# A300_Backplane.net
KiCad netlist of a schematic drawn in Altium Designer
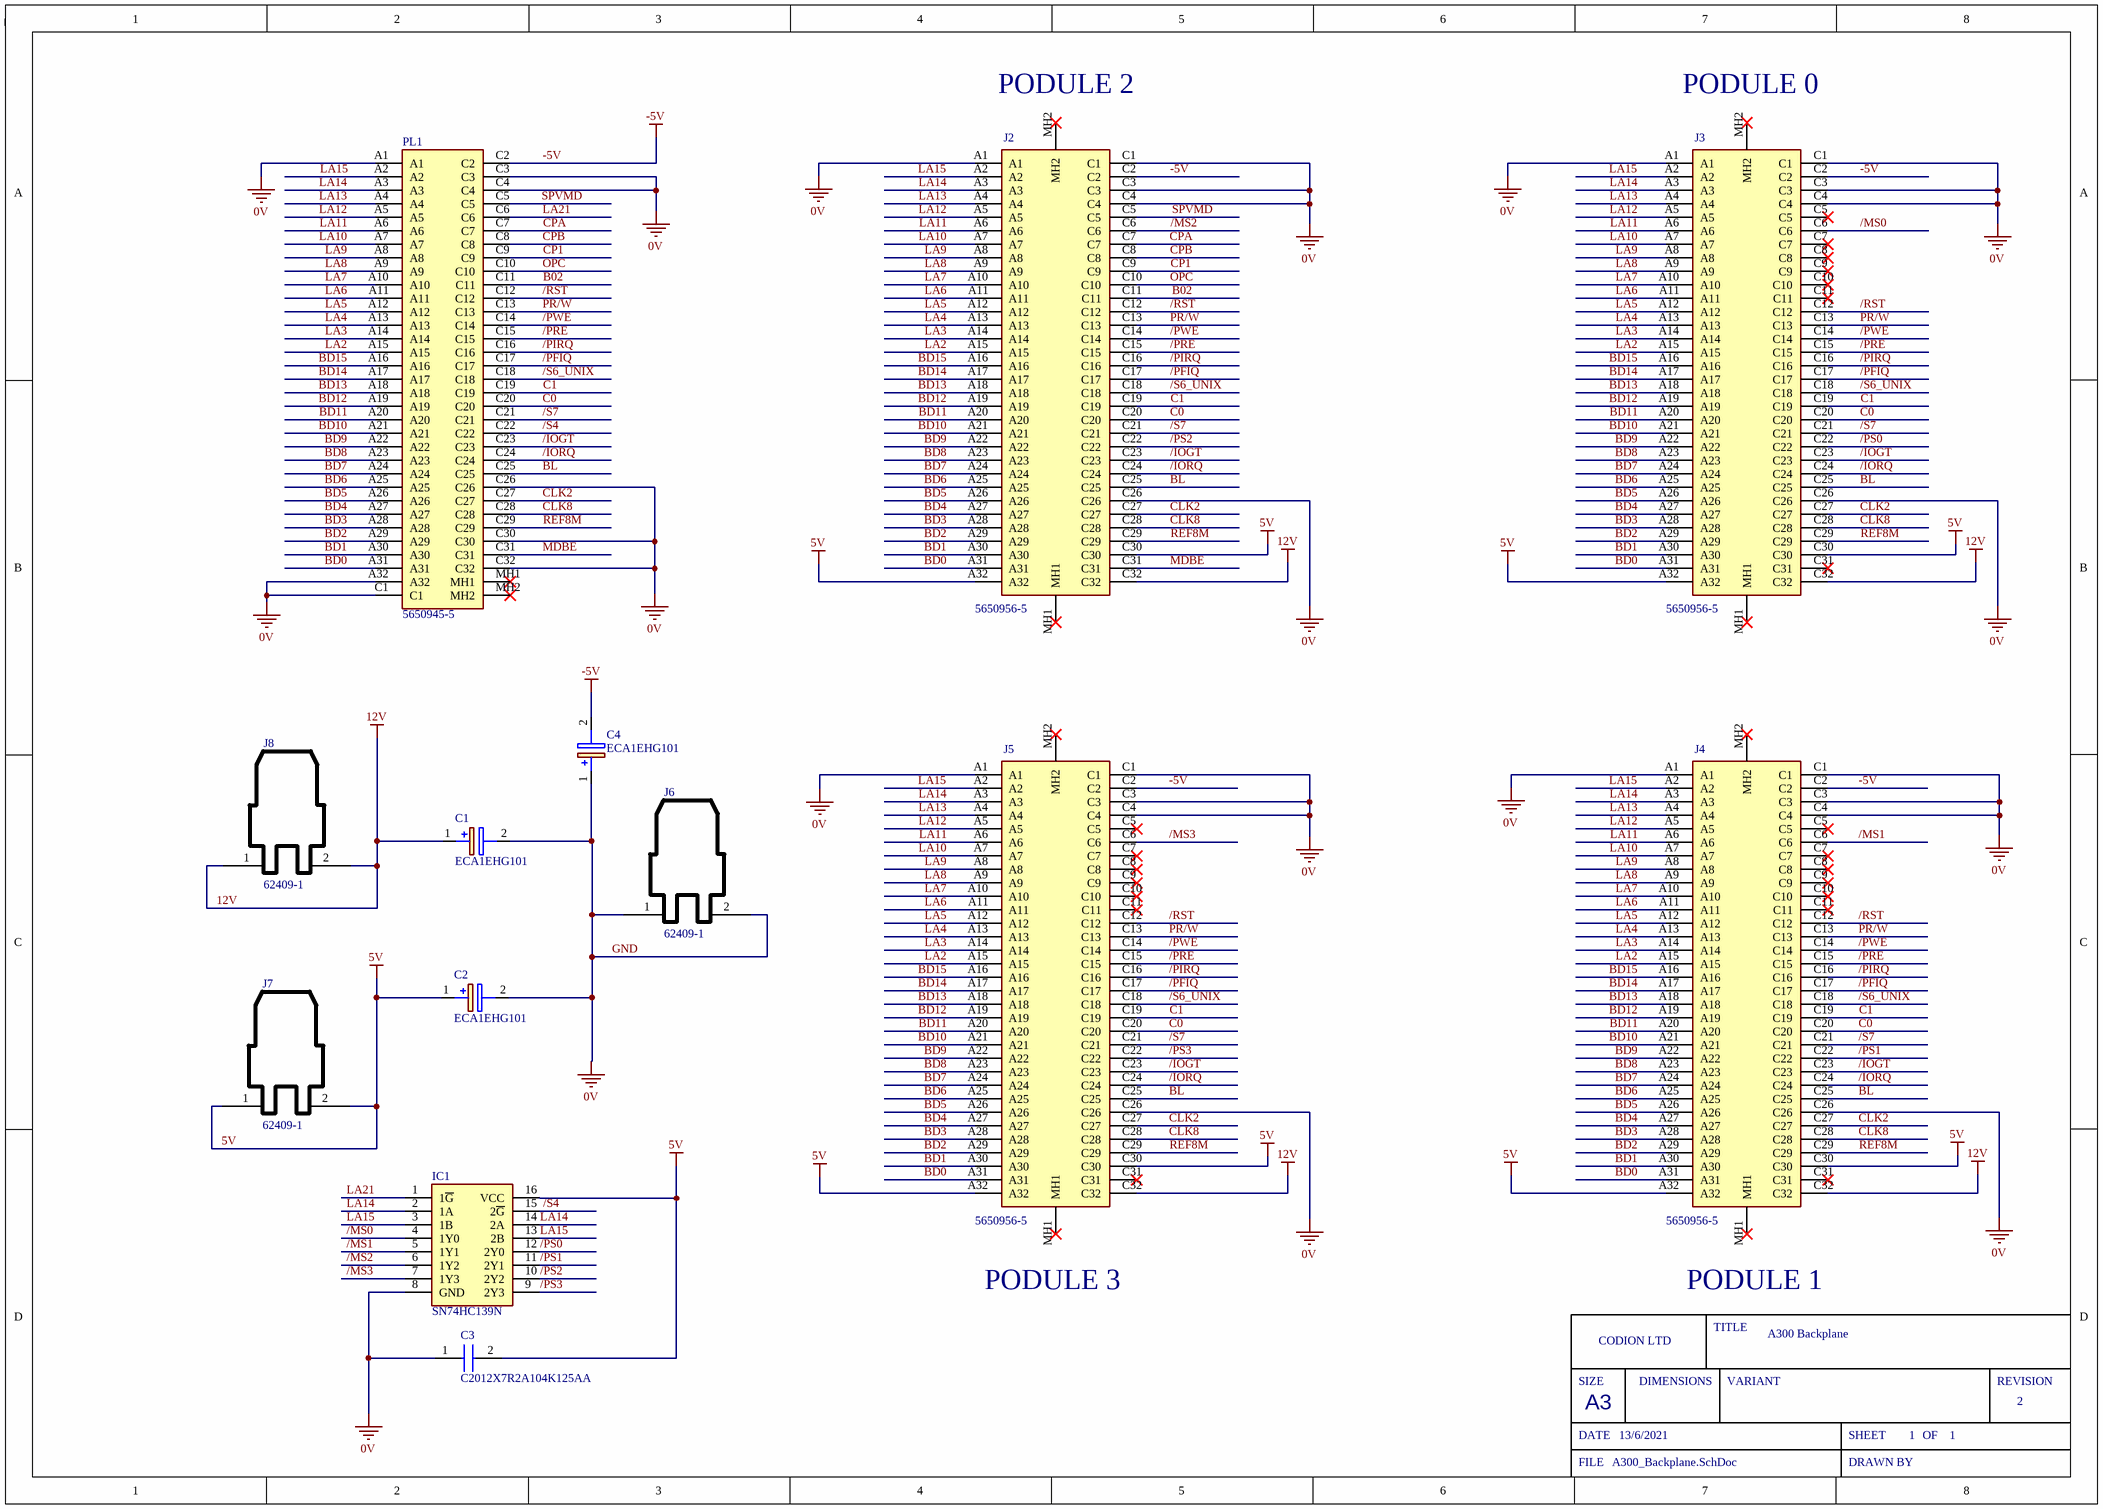
[diagram p0: A300_Backplane.SchDoc]

(export (version "E")
  (design (tool "Eeschema 10.0.6"))
  (components
    (comp (ref "C1")
      (value "ECA1EHG101")
      (footprint "SamacSys:CAPPRD250W55D630H1220")
      (description "Capacitor Polarised")
      (libsource (lib "") (part "ECA1EHG101_1"))
    )
    (comp (ref "C2")
      (value "ECA1EHG101")
      (footprint "SamacSys:CAPPRD250W55D630H1220")
      (description "Capacitor Polarised")
      (libsource (lib "") (part "ECA1EHG101_1"))
    )
    (comp (ref "C3")
      (value "C2012X7R2A104K125AA")
      (footprint "SamacSys:CAPC2012X145N")
      (description "Capacitor")
      (fields (field (name "MOUSER PART NUMBER") "810-C2012X7R2A104K"))
      (libsource (lib "*") (part "C2012X7R2A104K125AA"))
    )
    (comp (ref "C4")
      (value "ECA1EHG101")
      (footprint "SamacSys:CAPPRD250W55D630H1220")
      (description "Capacitor Polarised")
      (libsource (lib "*") (part "ECA1EHG101"))
    )
    (comp (ref "IC1")
      (value "SN74HC139N")
      (footprint "SamacSys:DIP794W53P254L1930H508Q16N")
      (description "Integrated Circuit")
      (fields (field (name "MOUSER PART NUMBER") "595-SN74HC139N"))
      (libsource (lib "*") (part "SN74HC139N"))
    )
    (comp (ref "J2")
      (value "5650956-5")
      (footprint "SamacSys:56509565")
      (description "Connector")
      (fields (field (name "MOUSER PART NUMBER") "571-5650956-5"))
      (libsource (lib "*") (part "5650956-5"))
    )
    (comp (ref "J3")
      (value "5650956-5")
      (footprint "SamacSys:56509565")
      (description "Connector")
      (fields (field (name "MOUSER PART NUMBER") "571-5650956-5"))
      (libsource (lib "*") (part "5650956-5"))
    )
    (comp (ref "J4")
      (value "5650956-5")
      (footprint "SamacSys:56509565")
      (description "Connector")
      (fields (field (name "MOUSER PART NUMBER") "571-5650956-5"))
      (libsource (lib "*") (part "5650956-5"))
    )
    (comp (ref "J5")
      (value "5650956-5")
      (footprint "SamacSys:56509565")
      (description "Connector")
      (fields (field (name "MOUSER PART NUMBER") "571-5650956-5"))
      (libsource (lib "*") (part "5650956-5"))
    )
    (comp (ref "J6")
      (value "62409-1")
      (footprint "62409-1")
      (description "PCB Terminal, 6.35mm x 0.81mm, 0.25\" x 0.032\", Brass, 1.4 mm, Tin")
      (fields (field (name "PART NUMBER") "982-0022") (field (name "MANUFACTURER") "TE Coonectivity"))
      (libsource (lib "Local_Altium_Lib") (part "62409-1"))
    )
    (comp (ref "J7")
      (value "62409-1")
      (footprint "62409-1")
      (description "PCB Terminal, 6.35mm x 0.81mm, 0.25\" x 0.032\", Brass, 1.4 mm, Tin")
      (fields (field (name "PART NUMBER") "982-0022") (field (name "MANUFACTURER") "TE Coonectivity"))
      (libsource (lib "Local_Altium_Lib") (part "62409-1"))
    )
    (comp (ref "J8")
      (value "62409-1")
      (footprint "62409-1")
      (description "PCB Terminal, 6.35mm x 0.81mm, 0.25\" x 0.032\", Brass, 1.4 mm, Tin")
      (fields (field (name "PART NUMBER") "982-0022") (field (name "MANUFACTURER") "TE Coonectivity"))
      (libsource (lib "Local_Altium_Lib") (part "62409-1"))
    )
    (comp (ref "PL1")
      (value "5650945-5")
      (footprint "SamacSys:56509455")
      (description "Connector")
      (fields (field (name "MOUSER PART NUMBER") "571-5650945-5"))
      (libsource (lib "*") (part "5650945-5"))
    )
  )
  (nets
    (net (code "1") (name "-5V") (class "Default")
      (node (ref "C4") (pin "2") (pinfunction "-_2") (pintype "passive"))
      (node (ref "J2") (pin "C2") (pinfunction "C2_C2") (pintype "passive"))
      (node (ref "J3") (pin "C2") (pinfunction "C2_C2") (pintype "passive"))
      (node (ref "J4") (pin "C2") (pinfunction "C2_C2") (pintype "passive"))
      (node (ref "J5") (pin "C2") (pinfunction "C2_C2") (pintype "passive"))
      (node (ref "PL1") (pin "C2") (pinfunction "C2_C2") (pintype "passive"))
    )
    (net (code "2") (name "/B02") (class "Default")
      (node (ref "J2") (pin "C11") (pinfunction "C11_C11") (pintype "passive"))
      (node (ref "PL1") (pin "C11") (pinfunction "C11_C11") (pintype "passive"))
    )
    (net (code "3") (name "/BD0") (class "Default")
      (node (ref "J2") (pin "A31") (pinfunction "A31_A31") (pintype "passive"))
      (node (ref "J3") (pin "A31") (pinfunction "A31_A31") (pintype "passive"))
      (node (ref "J4") (pin "A31") (pinfunction "A31_A31") (pintype "passive"))
      (node (ref "J5") (pin "A31") (pinfunction "A31_A31") (pintype "passive"))
      (node (ref "PL1") (pin "A31") (pinfunction "A31_A31") (pintype "passive"))
    )
    (net (code "4") (name "/BD1") (class "Default")
      (node (ref "J2") (pin "A30") (pinfunction "A30_A30") (pintype "passive"))
      (node (ref "J3") (pin "A30") (pinfunction "A30_A30") (pintype "passive"))
      (node (ref "J4") (pin "A30") (pinfunction "A30_A30") (pintype "passive"))
      (node (ref "J5") (pin "A30") (pinfunction "A30_A30") (pintype "passive"))
      (node (ref "PL1") (pin "A30") (pinfunction "A30_A30") (pintype "passive"))
    )
    (net (code "5") (name "/BD2") (class "Default")
      (node (ref "J2") (pin "A29") (pinfunction "A29_A29") (pintype "passive"))
      (node (ref "J3") (pin "A29") (pinfunction "A29_A29") (pintype "passive"))
      (node (ref "J4") (pin "A29") (pinfunction "A29_A29") (pintype "passive"))
      (node (ref "J5") (pin "A29") (pinfunction "A29_A29") (pintype "passive"))
      (node (ref "PL1") (pin "A29") (pinfunction "A29_A29") (pintype "passive"))
    )
    (net (code "6") (name "/BD3") (class "Default")
      (node (ref "J2") (pin "A28") (pinfunction "A28_A28") (pintype "passive"))
      (node (ref "J3") (pin "A28") (pinfunction "A28_A28") (pintype "passive"))
      (node (ref "J4") (pin "A28") (pinfunction "A28_A28") (pintype "passive"))
      (node (ref "J5") (pin "A28") (pinfunction "A28_A28") (pintype "passive"))
      (node (ref "PL1") (pin "A28") (pinfunction "A28_A28") (pintype "passive"))
    )
    (net (code "7") (name "/BD4") (class "Default")
      (node (ref "J2") (pin "A27") (pinfunction "A27_A27") (pintype "passive"))
      (node (ref "J3") (pin "A27") (pinfunction "A27_A27") (pintype "passive"))
      (node (ref "J4") (pin "A27") (pinfunction "A27_A27") (pintype "passive"))
      (node (ref "J5") (pin "A27") (pinfunction "A27_A27") (pintype "passive"))
      (node (ref "PL1") (pin "A27") (pinfunction "A27_A27") (pintype "passive"))
    )
    (net (code "8") (name "/BD5") (class "Default")
      (node (ref "J2") (pin "A26") (pinfunction "A26_A26") (pintype "passive"))
      (node (ref "J3") (pin "A26") (pinfunction "A26_A26") (pintype "passive"))
      (node (ref "J4") (pin "A26") (pinfunction "A26_A26") (pintype "passive"))
      (node (ref "J5") (pin "A26") (pinfunction "A26_A26") (pintype "passive"))
      (node (ref "PL1") (pin "A26") (pinfunction "A26_A26") (pintype "passive"))
    )
    (net (code "9") (name "/BD6") (class "Default")
      (node (ref "J2") (pin "A25") (pinfunction "A25_A25") (pintype "passive"))
      (node (ref "J3") (pin "A25") (pinfunction "A25_A25") (pintype "passive"))
      (node (ref "J4") (pin "A25") (pinfunction "A25_A25") (pintype "passive"))
      (node (ref "J5") (pin "A25") (pinfunction "A25_A25") (pintype "passive"))
      (node (ref "PL1") (pin "A25") (pinfunction "A25_A25") (pintype "passive"))
    )
    (net (code "10") (name "/BD7") (class "Default")
      (node (ref "J2") (pin "A24") (pinfunction "A24_A24") (pintype "passive"))
      (node (ref "J3") (pin "A24") (pinfunction "A24_A24") (pintype "passive"))
      (node (ref "J4") (pin "A24") (pinfunction "A24_A24") (pintype "passive"))
      (node (ref "J5") (pin "A24") (pinfunction "A24_A24") (pintype "passive"))
      (node (ref "PL1") (pin "A24") (pinfunction "A24_A24") (pintype "passive"))
    )
    (net (code "11") (name "/BD8") (class "Default")
      (node (ref "J2") (pin "A23") (pinfunction "A23_A23") (pintype "passive"))
      (node (ref "J3") (pin "A23") (pinfunction "A23_A23") (pintype "passive"))
      (node (ref "J4") (pin "A23") (pinfunction "A23_A23") (pintype "passive"))
      (node (ref "J5") (pin "A23") (pinfunction "A23_A23") (pintype "passive"))
      (node (ref "PL1") (pin "A23") (pinfunction "A23_A23") (pintype "passive"))
    )
    (net (code "12") (name "/BD9") (class "Default")
      (node (ref "J2") (pin "A22") (pinfunction "A22_A22") (pintype "passive"))
      (node (ref "J3") (pin "A22") (pinfunction "A22_A22") (pintype "passive"))
      (node (ref "J4") (pin "A22") (pinfunction "A22_A22") (pintype "passive"))
      (node (ref "J5") (pin "A22") (pinfunction "A22_A22") (pintype "passive"))
      (node (ref "PL1") (pin "A22") (pinfunction "A22_A22") (pintype "passive"))
    )
    (net (code "13") (name "/BD10") (class "Default")
      (node (ref "J2") (pin "A21") (pinfunction "A21_A21") (pintype "passive"))
      (node (ref "J3") (pin "A21") (pinfunction "A21_A21") (pintype "passive"))
      (node (ref "J4") (pin "A21") (pinfunction "A21_A21") (pintype "passive"))
      (node (ref "J5") (pin "A21") (pinfunction "A21_A21") (pintype "passive"))
      (node (ref "PL1") (pin "A21") (pinfunction "A21_A21") (pintype "passive"))
    )
    (net (code "14") (name "/BD11") (class "Default")
      (node (ref "J2") (pin "A20") (pinfunction "A20_A20") (pintype "passive"))
      (node (ref "J3") (pin "A20") (pinfunction "A20_A20") (pintype "passive"))
      (node (ref "J4") (pin "A20") (pinfunction "A20_A20") (pintype "passive"))
      (node (ref "J5") (pin "A20") (pinfunction "A20_A20") (pintype "passive"))
      (node (ref "PL1") (pin "A20") (pinfunction "A20_A20") (pintype "passive"))
    )
    (net (code "15") (name "/BD12") (class "Default")
      (node (ref "J2") (pin "A19") (pinfunction "A19_A19") (pintype "passive"))
      (node (ref "J3") (pin "A19") (pinfunction "A19_A19") (pintype "passive"))
      (node (ref "J4") (pin "A19") (pinfunction "A19_A19") (pintype "passive"))
      (node (ref "J5") (pin "A19") (pinfunction "A19_A19") (pintype "passive"))
      (node (ref "PL1") (pin "A19") (pinfunction "A19_A19") (pintype "passive"))
    )
    (net (code "16") (name "/BD13") (class "Default")
      (node (ref "J2") (pin "A18") (pinfunction "A18_A18") (pintype "passive"))
      (node (ref "J3") (pin "A18") (pinfunction "A18_A18") (pintype "passive"))
      (node (ref "J4") (pin "A18") (pinfunction "A18_A18") (pintype "passive"))
      (node (ref "J5") (pin "A18") (pinfunction "A18_A18") (pintype "passive"))
      (node (ref "PL1") (pin "A18") (pinfunction "A18_A18") (pintype "passive"))
    )
    (net (code "17") (name "/BD14") (class "Default")
      (node (ref "J2") (pin "A17") (pinfunction "A17_A17") (pintype "passive"))
      (node (ref "J3") (pin "A17") (pinfunction "A17_A17") (pintype "passive"))
      (node (ref "J4") (pin "A17") (pinfunction "A17_A17") (pintype "passive"))
      (node (ref "J5") (pin "A17") (pinfunction "A17_A17") (pintype "passive"))
      (node (ref "PL1") (pin "A17") (pinfunction "A17_A17") (pintype "passive"))
    )
    (net (code "18") (name "/BD15") (class "Default")
      (node (ref "J2") (pin "A16") (pinfunction "A16_A16") (pintype "passive"))
      (node (ref "J3") (pin "A16") (pinfunction "A16_A16") (pintype "passive"))
      (node (ref "J4") (pin "A16") (pinfunction "A16_A16") (pintype "passive"))
      (node (ref "J5") (pin "A16") (pinfunction "A16_A16") (pintype "passive"))
      (node (ref "PL1") (pin "A16") (pinfunction "A16_A16") (pintype "passive"))
    )
    (net (code "19") (name "/BL") (class "Default")
      (node (ref "J2") (pin "C25") (pinfunction "C25_C25") (pintype "passive"))
      (node (ref "J3") (pin "C25") (pinfunction "C25_C25") (pintype "passive"))
      (node (ref "J4") (pin "C25") (pinfunction "C25_C25") (pintype "passive"))
      (node (ref "J5") (pin "C25") (pinfunction "C25_C25") (pintype "passive"))
      (node (ref "PL1") (pin "C25") (pinfunction "C25_C25") (pintype "passive"))
    )
    (net (code "20") (name "/C0") (class "Default")
      (node (ref "J2") (pin "C20") (pinfunction "C20_C20") (pintype "passive"))
      (node (ref "J3") (pin "C20") (pinfunction "C20_C20") (pintype "passive"))
      (node (ref "J4") (pin "C20") (pinfunction "C20_C20") (pintype "passive"))
      (node (ref "J5") (pin "C20") (pinfunction "C20_C20") (pintype "passive"))
      (node (ref "PL1") (pin "C20") (pinfunction "C20_C20") (pintype "passive"))
    )
    (net (code "21") (name "/C1") (class "Default")
      (node (ref "J2") (pin "C19") (pinfunction "C19_C19") (pintype "passive"))
      (node (ref "J3") (pin "C19") (pinfunction "C19_C19") (pintype "passive"))
      (node (ref "J4") (pin "C19") (pinfunction "C19_C19") (pintype "passive"))
      (node (ref "J5") (pin "C19") (pinfunction "C19_C19") (pintype "passive"))
      (node (ref "PL1") (pin "C19") (pinfunction "C19_C19") (pintype "passive"))
    )
    (net (code "22") (name "/CLK2") (class "Default")
      (node (ref "J2") (pin "C27") (pinfunction "C27_C27") (pintype "passive"))
      (node (ref "J3") (pin "C27") (pinfunction "C27_C27") (pintype "passive"))
      (node (ref "J4") (pin "C27") (pinfunction "C27_C27") (pintype "passive"))
      (node (ref "J5") (pin "C27") (pinfunction "C27_C27") (pintype "passive"))
      (node (ref "PL1") (pin "C27") (pinfunction "C27_C27") (pintype "passive"))
    )
    (net (code "23") (name "/CLK8") (class "Default")
      (node (ref "J2") (pin "C28") (pinfunction "C28_C28") (pintype "passive"))
      (node (ref "J3") (pin "C28") (pinfunction "C28_C28") (pintype "passive"))
      (node (ref "J4") (pin "C28") (pinfunction "C28_C28") (pintype "passive"))
      (node (ref "J5") (pin "C28") (pinfunction "C28_C28") (pintype "passive"))
      (node (ref "PL1") (pin "C28") (pinfunction "C28_C28") (pintype "passive"))
    )
    (net (code "24") (name "/CP1") (class "Default")
      (node (ref "J2") (pin "C9") (pinfunction "C9_C9") (pintype "passive"))
      (node (ref "PL1") (pin "C9") (pinfunction "C9_C9") (pintype "passive"))
    )
    (net (code "25") (name "/CPA") (class "Default")
      (node (ref "J2") (pin "C7") (pinfunction "C7_C7") (pintype "passive"))
      (node (ref "PL1") (pin "C7") (pinfunction "C7_C7") (pintype "passive"))
    )
    (net (code "26") (name "/CPB") (class "Default")
      (node (ref "J2") (pin "C8") (pinfunction "C8_C8") (pintype "passive"))
      (node (ref "PL1") (pin "C8") (pinfunction "C8_C8") (pintype "passive"))
    )
    (net (code "27") (name "/LA2") (class "Default")
      (node (ref "J2") (pin "A15") (pinfunction "A15_A15") (pintype "passive"))
      (node (ref "J3") (pin "A15") (pinfunction "A15_A15") (pintype "passive"))
      (node (ref "J4") (pin "A15") (pinfunction "A15_A15") (pintype "passive"))
      (node (ref "J5") (pin "A15") (pinfunction "A15_A15") (pintype "passive"))
      (node (ref "PL1") (pin "A15") (pinfunction "A15_A15") (pintype "passive"))
    )
    (net (code "28") (name "/LA3") (class "Default")
      (node (ref "J2") (pin "A14") (pinfunction "A14_A14") (pintype "passive"))
      (node (ref "J3") (pin "A14") (pinfunction "A14_A14") (pintype "passive"))
      (node (ref "J4") (pin "A14") (pinfunction "A14_A14") (pintype "passive"))
      (node (ref "J5") (pin "A14") (pinfunction "A14_A14") (pintype "passive"))
      (node (ref "PL1") (pin "A14") (pinfunction "A14_A14") (pintype "passive"))
    )
    (net (code "29") (name "/LA4") (class "Default")
      (node (ref "J2") (pin "A13") (pinfunction "A13_A13") (pintype "passive"))
      (node (ref "J3") (pin "A13") (pinfunction "A13_A13") (pintype "passive"))
      (node (ref "J4") (pin "A13") (pinfunction "A13_A13") (pintype "passive"))
      (node (ref "J5") (pin "A13") (pinfunction "A13_A13") (pintype "passive"))
      (node (ref "PL1") (pin "A13") (pinfunction "A13_A13") (pintype "passive"))
    )
    (net (code "30") (name "/LA5") (class "Default")
      (node (ref "J2") (pin "A12") (pinfunction "A12_A12") (pintype "passive"))
      (node (ref "J3") (pin "A12") (pinfunction "A12_A12") (pintype "passive"))
      (node (ref "J4") (pin "A12") (pinfunction "A12_A12") (pintype "passive"))
      (node (ref "J5") (pin "A12") (pinfunction "A12_A12") (pintype "passive"))
      (node (ref "PL1") (pin "A12") (pinfunction "A12_A12") (pintype "passive"))
    )
    (net (code "31") (name "/LA6") (class "Default")
      (node (ref "J2") (pin "A11") (pinfunction "A11_A11") (pintype "passive"))
      (node (ref "J3") (pin "A11") (pinfunction "A11_A11") (pintype "passive"))
      (node (ref "J4") (pin "A11") (pinfunction "A11_A11") (pintype "passive"))
      (node (ref "J5") (pin "A11") (pinfunction "A11_A11") (pintype "passive"))
      (node (ref "PL1") (pin "A11") (pinfunction "A11_A11") (pintype "passive"))
    )
    (net (code "32") (name "/LA7") (class "Default")
      (node (ref "J2") (pin "A10") (pinfunction "A10_A10") (pintype "passive"))
      (node (ref "J3") (pin "A10") (pinfunction "A10_A10") (pintype "passive"))
      (node (ref "J4") (pin "A10") (pinfunction "A10_A10") (pintype "passive"))
      (node (ref "J5") (pin "A10") (pinfunction "A10_A10") (pintype "passive"))
      (node (ref "PL1") (pin "A10") (pinfunction "A10_A10") (pintype "passive"))
    )
    (net (code "33") (name "/LA8") (class "Default")
      (node (ref "J2") (pin "A9") (pinfunction "A9_A9") (pintype "passive"))
      (node (ref "J3") (pin "A9") (pinfunction "A9_A9") (pintype "passive"))
      (node (ref "J4") (pin "A9") (pinfunction "A9_A9") (pintype "passive"))
      (node (ref "J5") (pin "A9") (pinfunction "A9_A9") (pintype "passive"))
      (node (ref "PL1") (pin "A9") (pinfunction "A9_A9") (pintype "passive"))
    )
    (net (code "34") (name "/LA9") (class "Default")
      (node (ref "J2") (pin "A8") (pinfunction "A8_A8") (pintype "passive"))
      (node (ref "J3") (pin "A8") (pinfunction "A8_A8") (pintype "passive"))
      (node (ref "J4") (pin "A8") (pinfunction "A8_A8") (pintype "passive"))
      (node (ref "J5") (pin "A8") (pinfunction "A8_A8") (pintype "passive"))
      (node (ref "PL1") (pin "A8") (pinfunction "A8_A8") (pintype "passive"))
    )
    (net (code "35") (name "/LA10") (class "Default")
      (node (ref "J2") (pin "A7") (pinfunction "A7_A7") (pintype "passive"))
      (node (ref "J3") (pin "A7") (pinfunction "A7_A7") (pintype "passive"))
      (node (ref "J4") (pin "A7") (pinfunction "A7_A7") (pintype "passive"))
      (node (ref "J5") (pin "A7") (pinfunction "A7_A7") (pintype "passive"))
      (node (ref "PL1") (pin "A7") (pinfunction "A7_A7") (pintype "passive"))
    )
    (net (code "36") (name "/LA11") (class "Default")
      (node (ref "J2") (pin "A6") (pinfunction "A6_A6") (pintype "passive"))
      (node (ref "J3") (pin "A6") (pinfunction "A6_A6") (pintype "passive"))
      (node (ref "J4") (pin "A6") (pinfunction "A6_A6") (pintype "passive"))
      (node (ref "J5") (pin "A6") (pinfunction "A6_A6") (pintype "passive"))
      (node (ref "PL1") (pin "A6") (pinfunction "A6_A6") (pintype "passive"))
    )
    (net (code "37") (name "/LA12") (class "Default")
      (node (ref "J2") (pin "A5") (pinfunction "A5_A5") (pintype "passive"))
      (node (ref "J3") (pin "A5") (pinfunction "A5_A5") (pintype "passive"))
      (node (ref "J4") (pin "A5") (pinfunction "A5_A5") (pintype "passive"))
      (node (ref "J5") (pin "A5") (pinfunction "A5_A5") (pintype "passive"))
      (node (ref "PL1") (pin "A5") (pinfunction "A5_A5") (pintype "passive"))
    )
    (net (code "38") (name "/LA13") (class "Default")
      (node (ref "J2") (pin "A4") (pinfunction "A4_A4") (pintype "passive"))
      (node (ref "J3") (pin "A4") (pinfunction "A4_A4") (pintype "passive"))
      (node (ref "J4") (pin "A4") (pinfunction "A4_A4") (pintype "passive"))
      (node (ref "J5") (pin "A4") (pinfunction "A4_A4") (pintype "passive"))
      (node (ref "PL1") (pin "A4") (pinfunction "A4_A4") (pintype "passive"))
    )
    (net (code "39") (name "/LA14") (class "Default")
      (node (ref "IC1") (pin "14") (pinfunction "2A_14") (pintype "passive"))
      (node (ref "IC1") (pin "2") (pinfunction "1A_2") (pintype "passive"))
      (node (ref "J2") (pin "A3") (pinfunction "A3_A3") (pintype "passive"))
      (node (ref "J3") (pin "A3") (pinfunction "A3_A3") (pintype "passive"))
      (node (ref "J4") (pin "A3") (pinfunction "A3_A3") (pintype "passive"))
      (node (ref "J5") (pin "A3") (pinfunction "A3_A3") (pintype "passive"))
      (node (ref "PL1") (pin "A3") (pinfunction "A3_A3") (pintype "passive"))
    )
    (net (code "40") (name "/LA15") (class "Default")
      (node (ref "IC1") (pin "13") (pinfunction "2B_13") (pintype "passive"))
      (node (ref "IC1") (pin "3") (pinfunction "1B_3") (pintype "passive"))
      (node (ref "J2") (pin "A2") (pinfunction "A2_A2") (pintype "passive"))
      (node (ref "J3") (pin "A2") (pinfunction "A2_A2") (pintype "passive"))
      (node (ref "J4") (pin "A2") (pinfunction "A2_A2") (pintype "passive"))
      (node (ref "J5") (pin "A2") (pinfunction "A2_A2") (pintype "passive"))
      (node (ref "PL1") (pin "A2") (pinfunction "A2_A2") (pintype "passive"))
    )
    (net (code "41") (name "/LA21") (class "Default")
      (node (ref "IC1") (pin "1") (pinfunction "1~{G}_1") (pintype "passive"))
      (node (ref "PL1") (pin "C6") (pinfunction "C6_C6") (pintype "passive"))
    )
    (net (code "42") (name "/MDBE") (class "Default")
      (node (ref "J2") (pin "C31") (pinfunction "C31_C31") (pintype "passive"))
      (node (ref "PL1") (pin "C31") (pinfunction "C31_C31") (pintype "passive"))
    )
    (net (code "43") (name "/OPC") (class "Default")
      (node (ref "J2") (pin "C10") (pinfunction "C10_C10") (pintype "passive"))
      (node (ref "PL1") (pin "C10") (pinfunction "C10_C10") (pintype "passive"))
    )
    (net (code "44") (name "/PR{slash}W") (class "Default")
      (node (ref "J2") (pin "C13") (pinfunction "C13_C13") (pintype "passive"))
      (node (ref "J3") (pin "C13") (pinfunction "C13_C13") (pintype "passive"))
      (node (ref "J4") (pin "C13") (pinfunction "C13_C13") (pintype "passive"))
      (node (ref "J5") (pin "C13") (pinfunction "C13_C13") (pintype "passive"))
      (node (ref "PL1") (pin "C13") (pinfunction "C13_C13") (pintype "passive"))
    )
    (net (code "45") (name "/REF8M") (class "Default")
      (node (ref "J2") (pin "C29") (pinfunction "C29_C29") (pintype "passive"))
      (node (ref "J3") (pin "C29") (pinfunction "C29_C29") (pintype "passive"))
      (node (ref "J4") (pin "C29") (pinfunction "C29_C29") (pintype "passive"))
      (node (ref "J5") (pin "C29") (pinfunction "C29_C29") (pintype "passive"))
      (node (ref "PL1") (pin "C29") (pinfunction "C29_C29") (pintype "passive"))
    )
    (net (code "46") (name "/SPVMD") (class "Default")
      (node (ref "J2") (pin "C5") (pinfunction "C5_C5") (pintype "passive"))
      (node (ref "PL1") (pin "C5") (pinfunction "C5_C5") (pintype "passive"))
    )
    (net (code "47") (name "/{slash}IOGT") (class "Default")
      (node (ref "J2") (pin "C23") (pinfunction "C23_C23") (pintype "passive"))
      (node (ref "J3") (pin "C23") (pinfunction "C23_C23") (pintype "passive"))
      (node (ref "J4") (pin "C23") (pinfunction "C23_C23") (pintype "passive"))
      (node (ref "J5") (pin "C23") (pinfunction "C23_C23") (pintype "passive"))
      (node (ref "PL1") (pin "C23") (pinfunction "C23_C23") (pintype "passive"))
    )
    (net (code "48") (name "/{slash}IORQ") (class "Default")
      (node (ref "J2") (pin "C24") (pinfunction "C24_C24") (pintype "passive"))
      (node (ref "J3") (pin "C24") (pinfunction "C24_C24") (pintype "passive"))
      (node (ref "J4") (pin "C24") (pinfunction "C24_C24") (pintype "passive"))
      (node (ref "J5") (pin "C24") (pinfunction "C24_C24") (pintype "passive"))
      (node (ref "PL1") (pin "C24") (pinfunction "C24_C24") (pintype "passive"))
    )
    (net (code "49") (name "/{slash}MS0") (class "Default")
      (node (ref "IC1") (pin "4") (pinfunction "1Y0_4") (pintype "passive"))
      (node (ref "J3") (pin "C6") (pinfunction "C6_C6") (pintype "passive"))
    )
    (net (code "50") (name "/{slash}MS1") (class "Default")
      (node (ref "IC1") (pin "5") (pinfunction "1Y1_5") (pintype "passive"))
      (node (ref "J4") (pin "C6") (pinfunction "C6_C6") (pintype "passive"))
    )
    (net (code "51") (name "/{slash}MS2") (class "Default")
      (node (ref "IC1") (pin "6") (pinfunction "1Y2_6") (pintype "passive"))
      (node (ref "J2") (pin "C6") (pinfunction "C6_C6") (pintype "passive"))
    )
    (net (code "52") (name "/{slash}MS3") (class "Default")
      (node (ref "IC1") (pin "7") (pinfunction "1Y3_7") (pintype "passive"))
      (node (ref "J5") (pin "C6") (pinfunction "C6_C6") (pintype "passive"))
    )
    (net (code "53") (name "/{slash}PFIQ") (class "Default")
      (node (ref "J2") (pin "C17") (pinfunction "C17_C17") (pintype "passive"))
      (node (ref "J3") (pin "C17") (pinfunction "C17_C17") (pintype "passive"))
      (node (ref "J4") (pin "C17") (pinfunction "C17_C17") (pintype "passive"))
      (node (ref "J5") (pin "C17") (pinfunction "C17_C17") (pintype "passive"))
      (node (ref "PL1") (pin "C17") (pinfunction "C17_C17") (pintype "passive"))
    )
    (net (code "54") (name "/{slash}PIRQ") (class "Default")
      (node (ref "J2") (pin "C16") (pinfunction "C16_C16") (pintype "passive"))
      (node (ref "J3") (pin "C16") (pinfunction "C16_C16") (pintype "passive"))
      (node (ref "J4") (pin "C16") (pinfunction "C16_C16") (pintype "passive"))
      (node (ref "J5") (pin "C16") (pinfunction "C16_C16") (pintype "passive"))
      (node (ref "PL1") (pin "C16") (pinfunction "C16_C16") (pintype "passive"))
    )
    (net (code "55") (name "/{slash}PRE") (class "Default")
      (node (ref "J2") (pin "C15") (pinfunction "C15_C15") (pintype "passive"))
      (node (ref "J3") (pin "C15") (pinfunction "C15_C15") (pintype "passive"))
      (node (ref "J4") (pin "C15") (pinfunction "C15_C15") (pintype "passive"))
      (node (ref "J5") (pin "C15") (pinfunction "C15_C15") (pintype "passive"))
      (node (ref "PL1") (pin "C15") (pinfunction "C15_C15") (pintype "passive"))
    )
    (net (code "56") (name "/{slash}PS0") (class "Default")
      (node (ref "IC1") (pin "12") (pinfunction "2Y0_12") (pintype "passive"))
      (node (ref "J3") (pin "C22") (pinfunction "C22_C22") (pintype "passive"))
    )
    (net (code "57") (name "/{slash}PS1") (class "Default")
      (node (ref "IC1") (pin "11") (pinfunction "2Y1_11") (pintype "passive"))
      (node (ref "J4") (pin "C22") (pinfunction "C22_C22") (pintype "passive"))
    )
    (net (code "58") (name "/{slash}PS2") (class "Default")
      (node (ref "IC1") (pin "10") (pinfunction "2Y2_10") (pintype "passive"))
      (node (ref "J2") (pin "C22") (pinfunction "C22_C22") (pintype "passive"))
    )
    (net (code "59") (name "/{slash}PS3") (class "Default")
      (node (ref "IC1") (pin "9") (pinfunction "2Y3_9") (pintype "passive"))
      (node (ref "J5") (pin "C22") (pinfunction "C22_C22") (pintype "passive"))
    )
    (net (code "60") (name "/{slash}PWE") (class "Default")
      (node (ref "J2") (pin "C14") (pinfunction "C14_C14") (pintype "passive"))
      (node (ref "J3") (pin "C14") (pinfunction "C14_C14") (pintype "passive"))
      (node (ref "J4") (pin "C14") (pinfunction "C14_C14") (pintype "passive"))
      (node (ref "J5") (pin "C14") (pinfunction "C14_C14") (pintype "passive"))
      (node (ref "PL1") (pin "C14") (pinfunction "C14_C14") (pintype "passive"))
    )
    (net (code "61") (name "/{slash}RST") (class "Default")
      (node (ref "J2") (pin "C12") (pinfunction "C12_C12") (pintype "passive"))
      (node (ref "J3") (pin "C12") (pinfunction "C12_C12") (pintype "passive"))
      (node (ref "J4") (pin "C12") (pinfunction "C12_C12") (pintype "passive"))
      (node (ref "J5") (pin "C12") (pinfunction "C12_C12") (pintype "passive"))
      (node (ref "PL1") (pin "C12") (pinfunction "C12_C12") (pintype "passive"))
    )
    (net (code "62") (name "/{slash}S4") (class "Default")
      (node (ref "IC1") (pin "15") (pinfunction "2~{G}_15") (pintype "passive"))
      (node (ref "PL1") (pin "C22") (pinfunction "C22_C22") (pintype "passive"))
    )
    (net (code "63") (name "/{slash}S6_UNIX") (class "Default")
      (node (ref "J2") (pin "C18") (pinfunction "C18_C18") (pintype "passive"))
      (node (ref "J3") (pin "C18") (pinfunction "C18_C18") (pintype "passive"))
      (node (ref "J4") (pin "C18") (pinfunction "C18_C18") (pintype "passive"))
      (node (ref "J5") (pin "C18") (pinfunction "C18_C18") (pintype "passive"))
      (node (ref "PL1") (pin "C18") (pinfunction "C18_C18") (pintype "passive"))
    )
    (net (code "64") (name "/{slash}S7") (class "Default")
      (node (ref "J2") (pin "C21") (pinfunction "C21_C21") (pintype "passive"))
      (node (ref "J3") (pin "C21") (pinfunction "C21_C21") (pintype "passive"))
      (node (ref "J4") (pin "C21") (pinfunction "C21_C21") (pintype "passive"))
      (node (ref "J5") (pin "C21") (pinfunction "C21_C21") (pintype "passive"))
      (node (ref "PL1") (pin "C21") (pinfunction "C21_C21") (pintype "passive"))
    )
    (net (code "65") (name "0V") (class "Default")
      (node (ref "C1") (pin "2") (pinfunction "-_2") (pintype "passive"))
      (node (ref "C2") (pin "2") (pinfunction "-_2") (pintype "passive"))
      (node (ref "C3") (pin "1") (pinfunction "1_1") (pintype "passive"))
      (node (ref "C4") (pin "1") (pinfunction "+_1") (pintype "passive"))
      (node (ref "IC1") (pin "8") (pinfunction "GND_8") (pintype "passive"))
      (node (ref "J2") (pin "A1") (pinfunction "A1_A1") (pintype "passive"))
      (node (ref "J2") (pin "C1") (pinfunction "C1_C1") (pintype "passive"))
      (node (ref "J2") (pin "C26") (pinfunction "C26_C26") (pintype "passive"))
      (node (ref "J2") (pin "C3") (pinfunction "C3_C3") (pintype "passive"))
      (node (ref "J2") (pin "C4") (pinfunction "C4_C4") (pintype "passive"))
      (node (ref "J3") (pin "A1") (pinfunction "A1_A1") (pintype "passive"))
      (node (ref "J3") (pin "C1") (pinfunction "C1_C1") (pintype "passive"))
      (node (ref "J3") (pin "C26") (pinfunction "C26_C26") (pintype "passive"))
      (node (ref "J3") (pin "C3") (pinfunction "C3_C3") (pintype "passive"))
      (node (ref "J3") (pin "C4") (pinfunction "C4_C4") (pintype "passive"))
      (node (ref "J4") (pin "A1") (pinfunction "A1_A1") (pintype "passive"))
      (node (ref "J4") (pin "C1") (pinfunction "C1_C1") (pintype "passive"))
      (node (ref "J4") (pin "C26") (pinfunction "C26_C26") (pintype "passive"))
      (node (ref "J4") (pin "C3") (pinfunction "C3_C3") (pintype "passive"))
      (node (ref "J4") (pin "C4") (pinfunction "C4_C4") (pintype "passive"))
      (node (ref "J5") (pin "A1") (pinfunction "A1_A1") (pintype "passive"))
      (node (ref "J5") (pin "C1") (pinfunction "C1_C1") (pintype "passive"))
      (node (ref "J5") (pin "C26") (pinfunction "C26_C26") (pintype "passive"))
      (node (ref "J5") (pin "C3") (pinfunction "C3_C3") (pintype "passive"))
      (node (ref "J5") (pin "C4") (pinfunction "C4_C4") (pintype "passive"))
      (node (ref "J6") (pin "1") (pintype "power_in"))
      (node (ref "J6") (pin "2") (pintype "power_in"))
      (node (ref "PL1") (pin "A1") (pinfunction "A1_A1") (pintype "passive"))
      (node (ref "PL1") (pin "A32") (pinfunction "A32_A32") (pintype "passive"))
      (node (ref "PL1") (pin "C1") (pinfunction "C1_C1") (pintype "passive"))
      (node (ref "PL1") (pin "C26") (pinfunction "C26_C26") (pintype "passive"))
      (node (ref "PL1") (pin "C3") (pinfunction "C3_C3") (pintype "passive"))
      (node (ref "PL1") (pin "C30") (pinfunction "C30_C30") (pintype "passive"))
      (node (ref "PL1") (pin "C32") (pinfunction "C32_C32") (pintype "passive"))
      (node (ref "PL1") (pin "C4") (pinfunction "C4_C4") (pintype "passive"))
    )
    (net (code "66") (name "5V") (class "Default")
      (node (ref "C2") (pin "1") (pinfunction "+_1") (pintype "passive"))
      (node (ref "C3") (pin "2") (pinfunction "2_2") (pintype "passive"))
      (node (ref "IC1") (pin "16") (pinfunction "VCC_16") (pintype "passive"))
      (node (ref "J2") (pin "A32") (pinfunction "A32_A32") (pintype "passive"))
      (node (ref "J2") (pin "C30") (pinfunction "C30_C30") (pintype "passive"))
      (node (ref "J3") (pin "A32") (pinfunction "A32_A32") (pintype "passive"))
      (node (ref "J3") (pin "C30") (pinfunction "C30_C30") (pintype "passive"))
      (node (ref "J4") (pin "A32") (pinfunction "A32_A32") (pintype "passive"))
      (node (ref "J4") (pin "C30") (pinfunction "C30_C30") (pintype "passive"))
      (node (ref "J5") (pin "A32") (pinfunction "A32_A32") (pintype "passive"))
      (node (ref "J5") (pin "C30") (pinfunction "C30_C30") (pintype "passive"))
      (node (ref "J7") (pin "1") (pintype "power_in"))
      (node (ref "J7") (pin "2") (pintype "power_in"))
    )
    (net (code "67") (name "12V") (class "Default")
      (node (ref "C1") (pin "1") (pinfunction "+_1") (pintype "passive"))
      (node (ref "J2") (pin "C32") (pinfunction "C32_C32") (pintype "passive"))
      (node (ref "J3") (pin "C32") (pinfunction "C32_C32") (pintype "passive"))
      (node (ref "J4") (pin "C32") (pinfunction "C32_C32") (pintype "passive"))
      (node (ref "J5") (pin "C32") (pinfunction "C32_C32") (pintype "passive"))
      (node (ref "J8") (pin "1") (pintype "power_in"))
      (node (ref "J8") (pin "2") (pintype "power_in"))
    )
    (net (code "68") (name "unconnected-(J2-PadMH1)") (class "Default")
      (node (ref "J2") (pin "MH1") (pinfunction "MH1_MH1") (pintype "passive+no_connect"))
    )
    (net (code "69") (name "unconnected-(J2-PadMH2)") (class "Default")
      (node (ref "J2") (pin "MH2") (pinfunction "MH2_MH2") (pintype "passive+no_connect"))
    )
    (net (code "70") (name "unconnected-(J3-PadC5)") (class "Default")
      (node (ref "J3") (pin "C5") (pinfunction "C5_C5") (pintype "passive+no_connect"))
    )
    (net (code "71") (name "unconnected-(J3-PadC7)") (class "Default")
      (node (ref "J3") (pin "C7") (pinfunction "C7_C7") (pintype "passive+no_connect"))
    )
    (net (code "72") (name "unconnected-(J3-PadC8)") (class "Default")
      (node (ref "J3") (pin "C8") (pinfunction "C8_C8") (pintype "passive+no_connect"))
    )
    (net (code "73") (name "unconnected-(J3-PadC9)") (class "Default")
      (node (ref "J3") (pin "C9") (pinfunction "C9_C9") (pintype "passive+no_connect"))
    )
    (net (code "74") (name "unconnected-(J3-PadC10)") (class "Default")
      (node (ref "J3") (pin "C10") (pinfunction "C10_C10") (pintype "passive+no_connect"))
    )
    (net (code "75") (name "unconnected-(J3-PadC11)") (class "Default")
      (node (ref "J3") (pin "C11") (pinfunction "C11_C11") (pintype "passive+no_connect"))
    )
    (net (code "76") (name "unconnected-(J3-PadC31)") (class "Default")
      (node (ref "J3") (pin "C31") (pinfunction "C31_C31") (pintype "passive+no_connect"))
    )
    (net (code "77") (name "unconnected-(J3-PadMH1)") (class "Default")
      (node (ref "J3") (pin "MH1") (pinfunction "MH1_MH1") (pintype "passive+no_connect"))
    )
    (net (code "78") (name "unconnected-(J3-PadMH2)") (class "Default")
      (node (ref "J3") (pin "MH2") (pinfunction "MH2_MH2") (pintype "passive+no_connect"))
    )
    (net (code "79") (name "unconnected-(J4-PadC5)") (class "Default")
      (node (ref "J4") (pin "C5") (pinfunction "C5_C5") (pintype "passive+no_connect"))
    )
    (net (code "80") (name "unconnected-(J4-PadC7)") (class "Default")
      (node (ref "J4") (pin "C7") (pinfunction "C7_C7") (pintype "passive+no_connect"))
    )
    (net (code "81") (name "unconnected-(J4-PadC8)") (class "Default")
      (node (ref "J4") (pin "C8") (pinfunction "C8_C8") (pintype "passive+no_connect"))
    )
    (net (code "82") (name "unconnected-(J4-PadC9)") (class "Default")
      (node (ref "J4") (pin "C9") (pinfunction "C9_C9") (pintype "passive+no_connect"))
    )
    (net (code "83") (name "unconnected-(J4-PadC10)") (class "Default")
      (node (ref "J4") (pin "C10") (pinfunction "C10_C10") (pintype "passive+no_connect"))
    )
    (net (code "84") (name "unconnected-(J4-PadC11)") (class "Default")
      (node (ref "J4") (pin "C11") (pinfunction "C11_C11") (pintype "passive+no_connect"))
    )
    (net (code "85") (name "unconnected-(J4-PadC31)") (class "Default")
      (node (ref "J4") (pin "C31") (pinfunction "C31_C31") (pintype "passive+no_connect"))
    )
    (net (code "86") (name "unconnected-(J4-PadMH1)") (class "Default")
      (node (ref "J4") (pin "MH1") (pinfunction "MH1_MH1") (pintype "passive+no_connect"))
    )
    (net (code "87") (name "unconnected-(J4-PadMH2)") (class "Default")
      (node (ref "J4") (pin "MH2") (pinfunction "MH2_MH2") (pintype "passive+no_connect"))
    )
    (net (code "88") (name "unconnected-(J5-PadC5)") (class "Default")
      (node (ref "J5") (pin "C5") (pinfunction "C5_C5") (pintype "passive+no_connect"))
    )
    (net (code "89") (name "unconnected-(J5-PadC7)") (class "Default")
      (node (ref "J5") (pin "C7") (pinfunction "C7_C7") (pintype "passive+no_connect"))
    )
    (net (code "90") (name "unconnected-(J5-PadC8)") (class "Default")
      (node (ref "J5") (pin "C8") (pinfunction "C8_C8") (pintype "passive+no_connect"))
    )
    (net (code "91") (name "unconnected-(J5-PadC9)") (class "Default")
      (node (ref "J5") (pin "C9") (pinfunction "C9_C9") (pintype "passive+no_connect"))
    )
    (net (code "92") (name "unconnected-(J5-PadC10)") (class "Default")
      (node (ref "J5") (pin "C10") (pinfunction "C10_C10") (pintype "passive+no_connect"))
    )
    (net (code "93") (name "unconnected-(J5-PadC11)") (class "Default")
      (node (ref "J5") (pin "C11") (pinfunction "C11_C11") (pintype "passive+no_connect"))
    )
    (net (code "94") (name "unconnected-(J5-PadC31)") (class "Default")
      (node (ref "J5") (pin "C31") (pinfunction "C31_C31") (pintype "passive+no_connect"))
    )
    (net (code "95") (name "unconnected-(J5-PadMH1)") (class "Default")
      (node (ref "J5") (pin "MH1") (pinfunction "MH1_MH1") (pintype "passive+no_connect"))
    )
    (net (code "96") (name "unconnected-(J5-PadMH2)") (class "Default")
      (node (ref "J5") (pin "MH2") (pinfunction "MH2_MH2") (pintype "passive+no_connect"))
    )
    (net (code "97") (name "unconnected-(PL1-PadMH1)") (class "Default")
      (node (ref "PL1") (pin "MH1") (pinfunction "MH1_MH1") (pintype "passive+no_connect"))
    )
    (net (code "98") (name "unconnected-(PL1-PadMH2)") (class "Default")
      (node (ref "PL1") (pin "MH2") (pinfunction "MH2_MH2") (pintype "passive+no_connect"))
    )
  )
)
